# EEZ_DIB_BP3C_r1B4.net
KiCad netlist of a schematic drawn in EAGLE
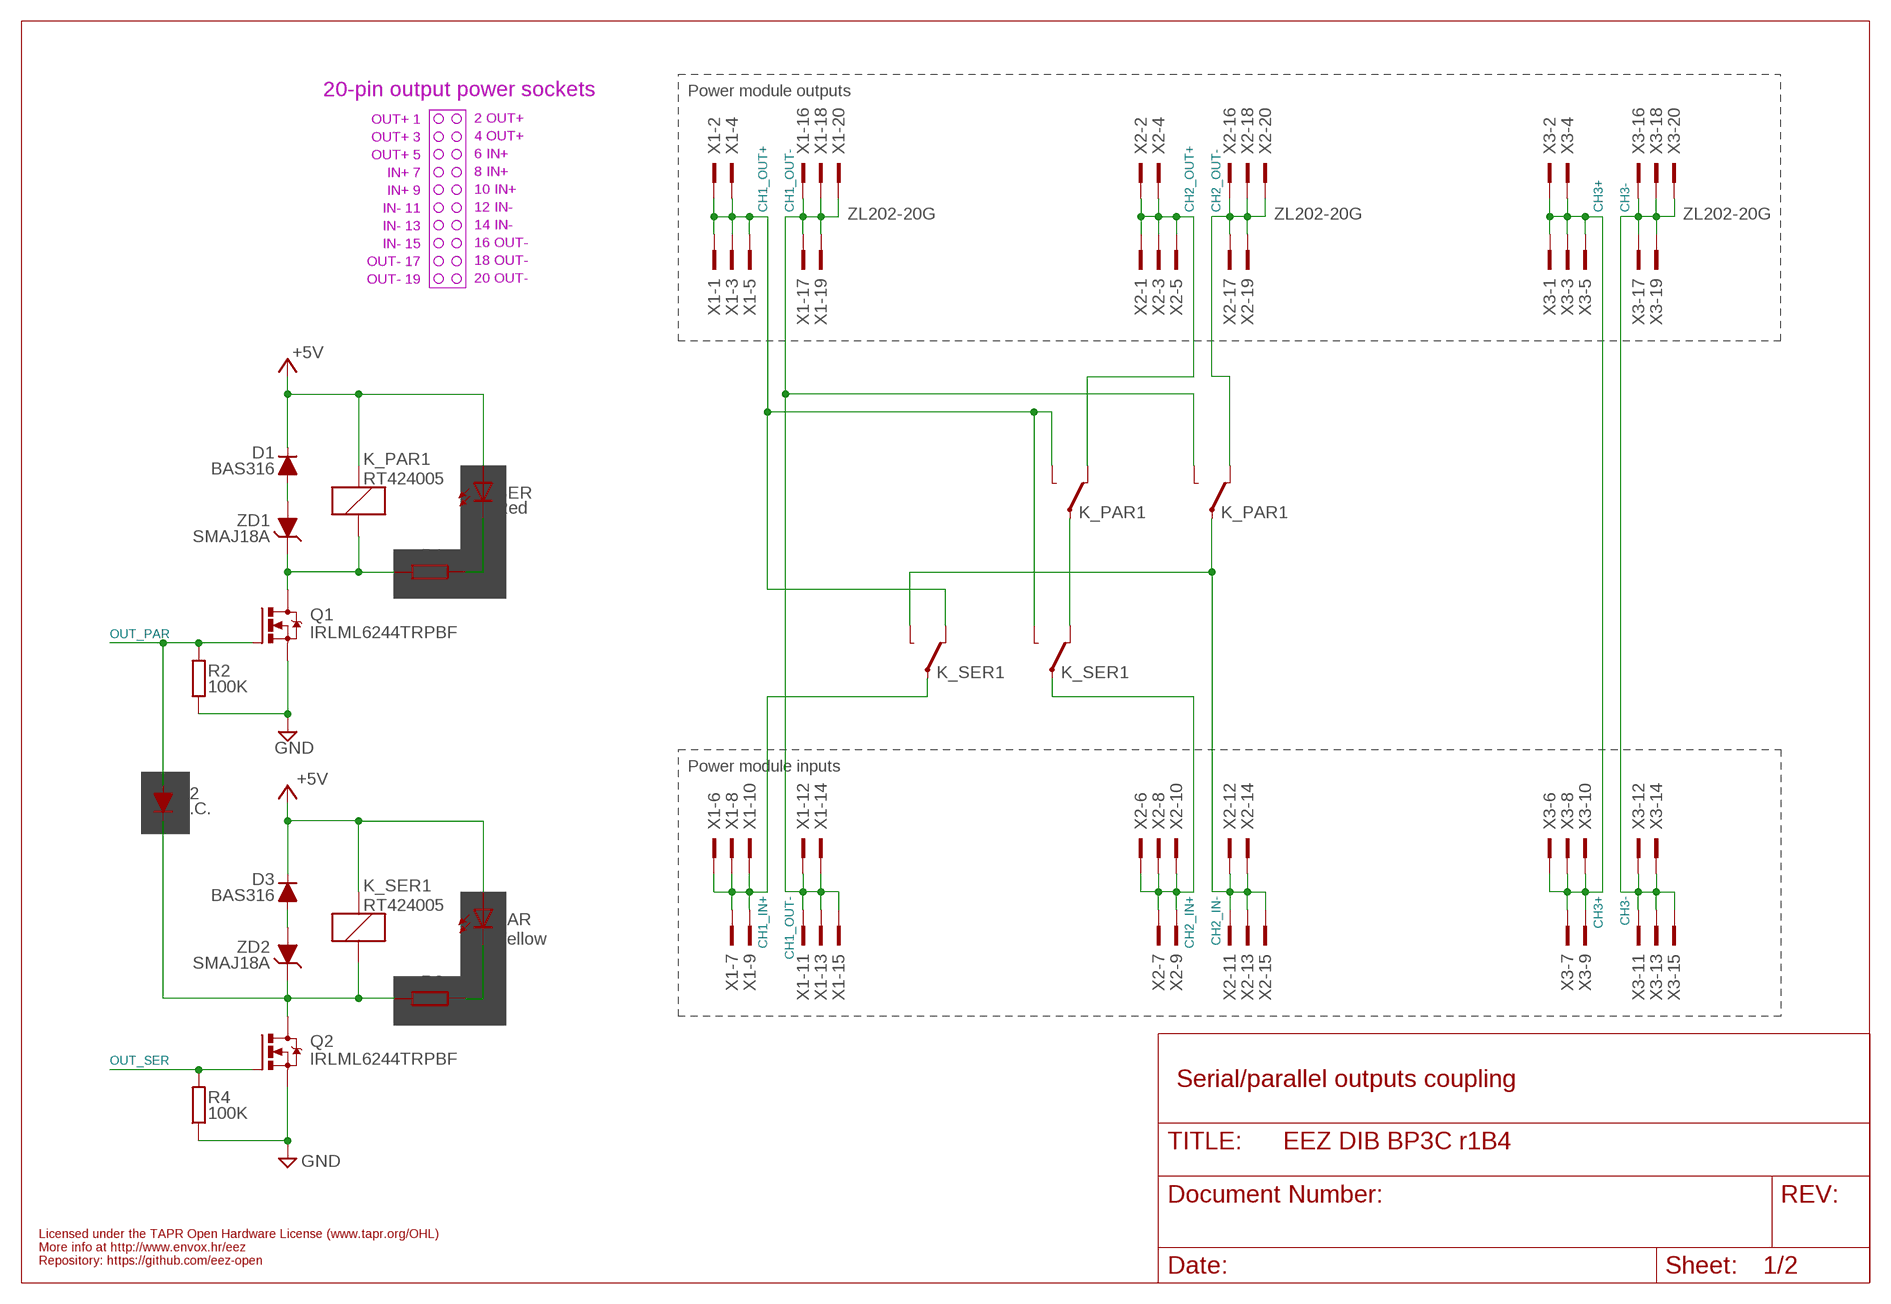
[diagram p0: schematic, sheet 1]
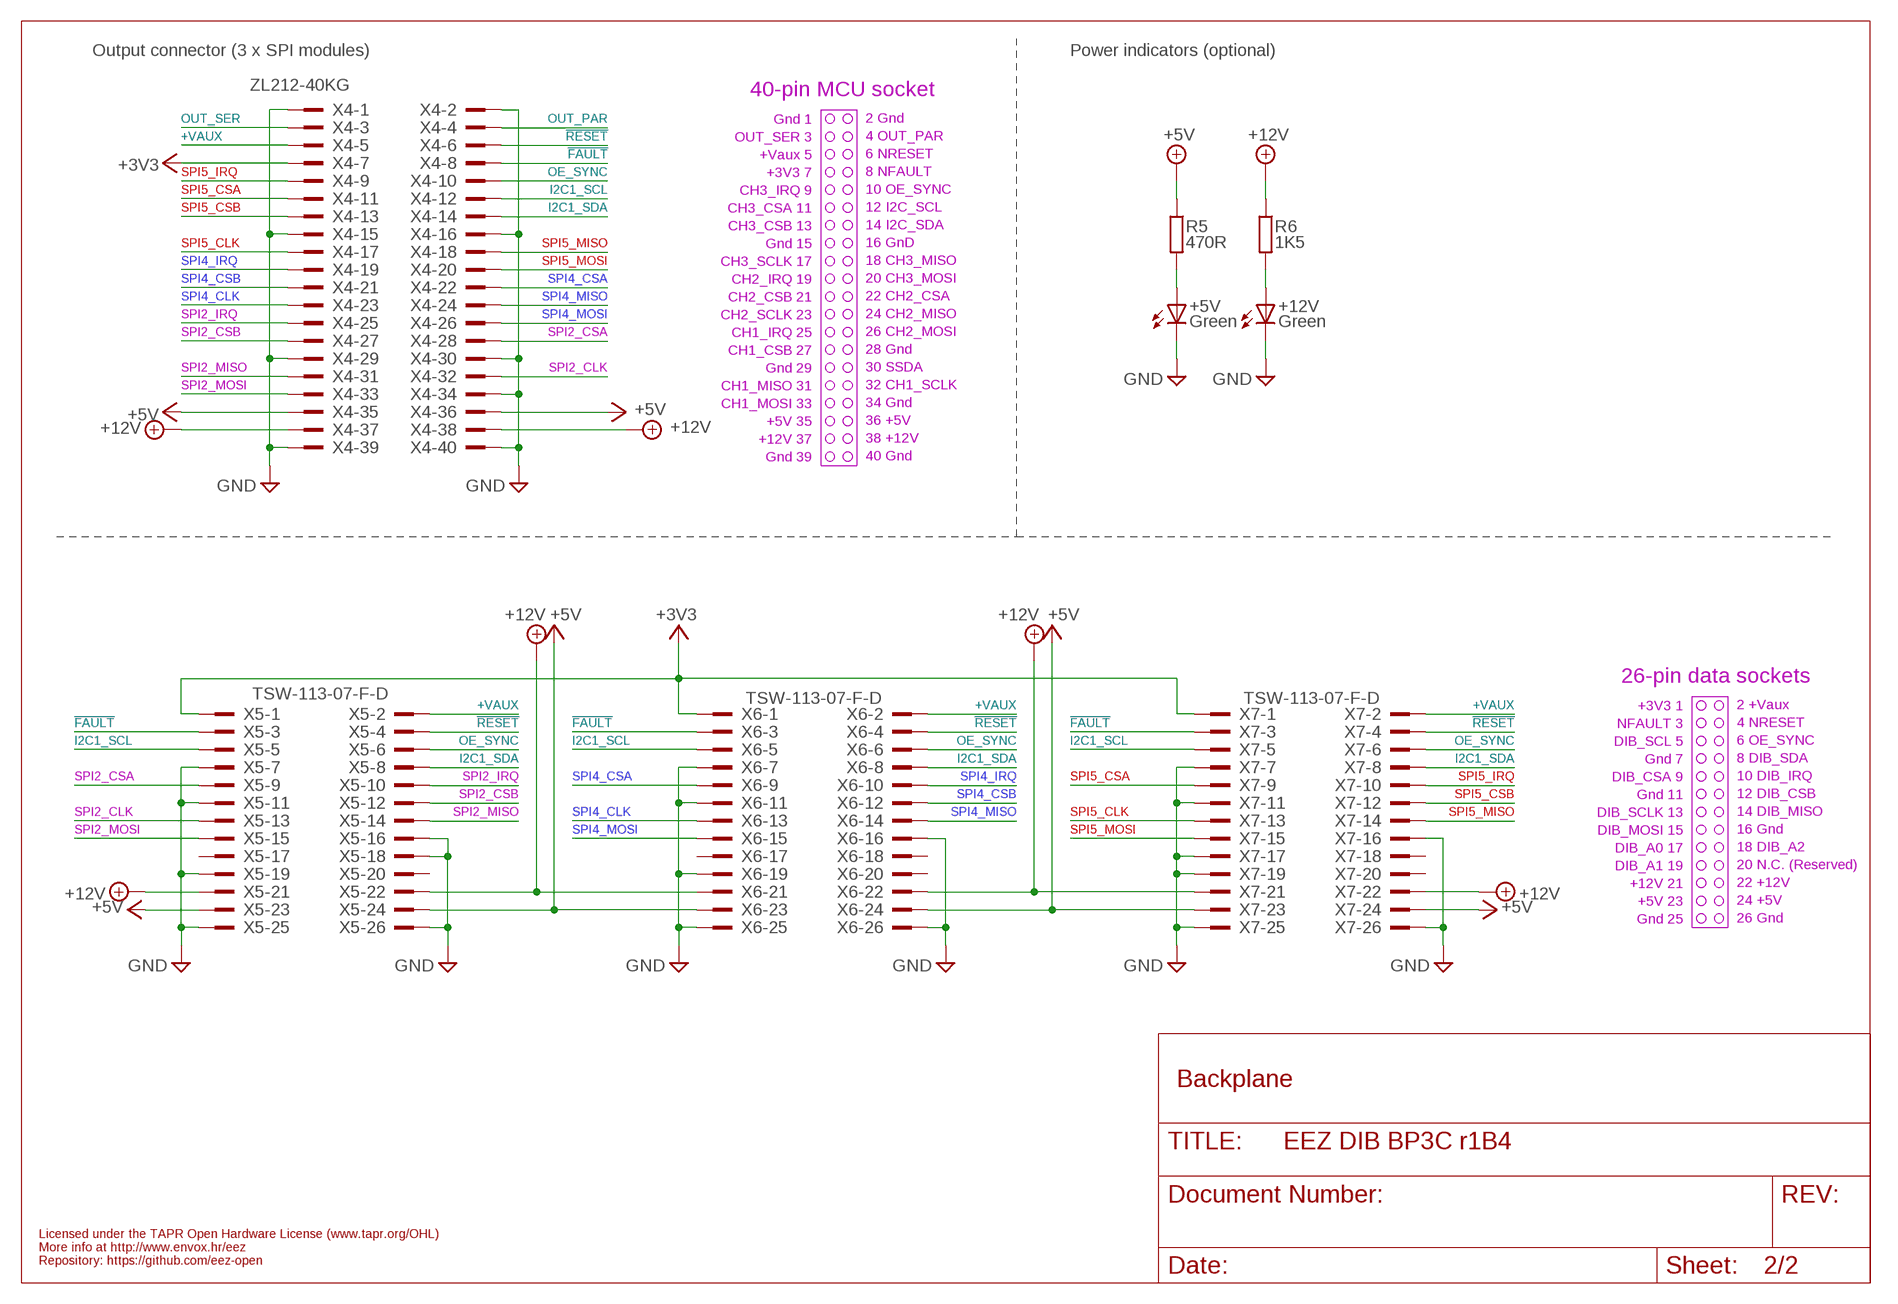
[diagram p1: schematic, sheet 2]

(export (version "E")
  (design (tool "Eeschema 10.0.6"))
  (components
    (comp (ref "+5V")
      (value "Green")
      (footprint "eagle-import:LED_0805")
      (libsource (lib "eagle-import") (part "LED0805"))
    )
    (comp (ref "+12V")
      (value "Green")
      (footprint "eagle-import:LED_0805")
      (libsource (lib "eagle-import") (part "LED0805"))
    )
    (comp (ref "R5")
      (value "470R")
      (footprint "eagle-import:R0805")
      (libsource (lib "eagle-import") (part "R-EU_R0805"))
    )
    (comp (ref "R6")
      (value "1K5")
      (footprint "eagle-import:R0805")
      (libsource (lib "eagle-import") (part "R-EU_R0805"))
    )
    (comp (ref "X4")
      (value "ZL212-40KG")
      (footprint "eagle-import:ZL212-40KG")
      (libsource (lib "eagle-import") (part "ZL212-40KG"))
    )
    (comp (ref "X5")
      (value "TSW-113-07-F-D")
      (footprint "eagle-import:TSW-113-07-F-D")
      (libsource (lib "eagle-import") (part "TSW-113-07-F-D"))
    )
    (comp (ref "X6")
      (value "TSW-113-07-F-D")
      (footprint "eagle-import:TSW-113-07-F-D")
      (libsource (lib "eagle-import") (part "TSW-113-07-F-D"))
    )
    (comp (ref "X7")
      (value "TSW-113-07-F-D")
      (footprint "eagle-import:TSW-113-07-F-D")
      (libsource (lib "eagle-import") (part "TSW-113-07-F-D"))
    )
    (comp (ref "D1")
      (value "BAS316")
      (footprint "eagle-import:SOD323-R")
      (libsource (lib "eagle-import") (part "DIODESOD323R"))
    )
    (comp (ref "D2")
      (value "N.C.")
      (footprint "eagle-import:SOD323-R")
      (libsource (lib "eagle-import") (part "DIODESOD323R"))
    )
    (comp (ref "D3")
      (value "BAS316")
      (footprint "eagle-import:SOD323-R")
      (libsource (lib "eagle-import") (part "DIODESOD323R"))
    )
    (comp (ref "K_PAR1")
      (value "RT424005")
      (footprint "eagle-import:RT-C_016A5_ROUND")
      (libsource (lib "eagle-import") (part "RELAY_RT314012-2"))
    )
    (comp (ref "K_SER1")
      (value "RT424005")
      (footprint "eagle-import:RT-C_016A5_ROUND")
      (libsource (lib "eagle-import") (part "RELAY_RT314012-2"))
    )
    (comp (ref "PAR")
      (value "Yellow")
      (footprint "eagle-import:LED_0805")
      (libsource (lib "eagle-import") (part "LED0805"))
    )
    (comp (ref "Q1")
      (value "IRLML6244TRPBF")
      (footprint "eagle-import:SOT103P240X110-3N")
      (fields
        (field (name "MPN") "2N7002-7-F")
        (field (name "MPN_1") "2N7002-7-F")
        (field (name "OC_FARNELL") "1713823")
        (field (name "OC_NEWARK") "25R5679")
        (field (name "PACKAGE") "SOT-23-3")
        (field (name "SUPPLIER") "DIODES INC.")
      )
      (libsource (lib "eagle-import") (part "2N7002"))
    )
    (comp (ref "Q2")
      (value "IRLML6244TRPBF")
      (footprint "eagle-import:SOT103P240X110-3N")
      (fields
        (field (name "MPN") "2N7002-7-F")
        (field (name "MPN_1") "2N7002-7-F")
        (field (name "OC_FARNELL") "1713823")
        (field (name "OC_NEWARK") "25R5679")
        (field (name "PACKAGE") "SOT-23-3")
        (field (name "SUPPLIER") "DIODES INC.")
      )
      (libsource (lib "eagle-import") (part "2N7002"))
    )
    (comp (ref "R1")
      (value "330R")
      (footprint "eagle-import:R0805")
      (libsource (lib "eagle-import") (part "R-EU_R0805"))
    )
    (comp (ref "R2")
      (value "100K")
      (footprint "eagle-import:R0805")
      (libsource (lib "eagle-import") (part "R-EU_R0805"))
    )
    (comp (ref "R3")
      (value "330R")
      (footprint "eagle-import:R0805")
      (libsource (lib "eagle-import") (part "R-EU_R0805"))
    )
    (comp (ref "R4")
      (value "100K")
      (footprint "eagle-import:R0805")
      (libsource (lib "eagle-import") (part "R-EU_R0805"))
    )
    (comp (ref "SER")
      (value "Red")
      (footprint "eagle-import:LED_0805")
      (libsource (lib "eagle-import") (part "LED0805"))
    )
    (comp (ref "X1")
      (value "ZL202-20G")
      (footprint "eagle-import:DS1021-2_10SF11")
      (libsource (lib "eagle-import") (part "DS1021-210SF11"))
    )
    (comp (ref "X2")
      (value "ZL202-20G")
      (footprint "eagle-import:DS1021-2_10SF11")
      (libsource (lib "eagle-import") (part "DS1021-210SF11"))
    )
    (comp (ref "X3")
      (value "ZL202-20G")
      (footprint "eagle-import:DS1021-2_10SF11")
      (libsource (lib "eagle-import") (part "DS1021-210SF11"))
    )
    (comp (ref "ZD1")
      (value "SMAJ18A")
      (footprint "eagle-import:DO214AC")
      (libsource (lib "eagle-import") (part "PSMAXX"))
    )
    (comp (ref "ZD2")
      (value "SMAJ18A")
      (footprint "eagle-import:DO214AC")
      (libsource (lib "eagle-import") (part "PSMAXX"))
    )
  )
  (nets
    (net (code "1") (name "+3V3") (class "Default")
      (node (ref "X4") (pin "7") (pinfunction "1_7") (pintype "passive"))
      (node (ref "X5") (pin "1") (pinfunction "1_1") (pintype "passive"))
      (node (ref "X6") (pin "1") (pinfunction "1_1") (pintype "passive"))
      (node (ref "X7") (pin "1") (pinfunction "1_1") (pintype "passive"))
    )
    (net (code "2") (name "+5V") (class "Default")
      (node (ref "D1") (pin "C") (pinfunction "C_C") (pintype "passive"))
      (node (ref "D3") (pin "C") (pinfunction "C_C") (pintype "passive"))
      (node (ref "K_PAR1") (pin "A2") (pinfunction "C1_A2") (pintype "passive"))
      (node (ref "K_SER1") (pin "A2") (pinfunction "C1_A2") (pintype "passive"))
      (node (ref "PAR") (pin "A") (pinfunction "A_A") (pintype "passive"))
      (node (ref "R5") (pin "1") (pinfunction "1_1") (pintype "passive"))
      (node (ref "SER") (pin "A") (pinfunction "A_A") (pintype "passive"))
      (node (ref "X4") (pin "35") (pinfunction "1_35") (pintype "passive"))
      (node (ref "X4") (pin "36") (pinfunction "1_36") (pintype "passive"))
      (node (ref "X5") (pin "23") (pinfunction "1_23") (pintype "passive"))
      (node (ref "X5") (pin "24") (pinfunction "1_24") (pintype "passive"))
      (node (ref "X6") (pin "23") (pinfunction "1_23") (pintype "passive"))
      (node (ref "X6") (pin "24") (pinfunction "1_24") (pintype "passive"))
      (node (ref "X7") (pin "23") (pinfunction "1_23") (pintype "passive"))
      (node (ref "X7") (pin "24") (pinfunction "1_24") (pintype "passive"))
    )
    (net (code "3") (name "+12V") (class "Default")
      (node (ref "R6") (pin "1") (pinfunction "1_1") (pintype "passive"))
      (node (ref "X4") (pin "37") (pinfunction "1_37") (pintype "passive"))
      (node (ref "X4") (pin "38") (pinfunction "1_38") (pintype "passive"))
      (node (ref "X5") (pin "21") (pinfunction "1_21") (pintype "passive"))
      (node (ref "X5") (pin "22") (pinfunction "1_22") (pintype "passive"))
      (node (ref "X6") (pin "21") (pinfunction "1_21") (pintype "passive"))
      (node (ref "X6") (pin "22") (pinfunction "1_22") (pintype "passive"))
      (node (ref "X7") (pin "21") (pinfunction "1_21") (pintype "passive"))
      (node (ref "X7") (pin "22") (pinfunction "1_22") (pintype "passive"))
    )
    (net (code "4") (name "+VAUX") (class "Default")
      (node (ref "X4") (pin "5") (pinfunction "1_5") (pintype "passive"))
      (node (ref "X5") (pin "2") (pinfunction "1_2") (pintype "passive"))
      (node (ref "X6") (pin "2") (pinfunction "1_2") (pintype "passive"))
      (node (ref "X7") (pin "2") (pinfunction "1_2") (pintype "passive"))
    )
    (net (code "5") (name "CH1_IN+") (class "Default")
      (node (ref "K_SER1") (pin "11A") (pinfunction "P_11A") (pintype "passive"))
      (node (ref "X1") (pin "10") (pinfunction "1_10") (pintype "passive"))
      (node (ref "X1") (pin "6") (pinfunction "1_6") (pintype "passive"))
      (node (ref "X1") (pin "7") (pinfunction "1_7") (pintype "passive"))
      (node (ref "X1") (pin "8") (pinfunction "1_8") (pintype "passive"))
      (node (ref "X1") (pin "9") (pinfunction "1_9") (pintype "passive"))
    )
    (net (code "6") (name "CH1_OUT+") (class "Default")
      (node (ref "K_PAR1") (pin "14A") (pinfunction "O_14A") (pintype "passive"))
      (node (ref "K_SER1") (pin "12A") (pinfunction "S_12A") (pintype "passive"))
      (node (ref "K_SER1") (pin "14B") (pinfunction "O_14B") (pintype "passive"))
      (node (ref "X1") (pin "1") (pinfunction "1_1") (pintype "passive"))
      (node (ref "X1") (pin "2") (pinfunction "1_2") (pintype "passive"))
      (node (ref "X1") (pin "3") (pinfunction "1_3") (pintype "passive"))
      (node (ref "X1") (pin "4") (pinfunction "1_4") (pintype "passive"))
      (node (ref "X1") (pin "5") (pinfunction "1_5") (pintype "passive"))
    )
    (net (code "7") (name "CH1_OUT-") (class "Default")
      (node (ref "K_PAR1") (pin "14B") (pinfunction "O_14B") (pintype "passive"))
      (node (ref "X1") (pin "11") (pinfunction "1_11") (pintype "passive"))
      (node (ref "X1") (pin "12") (pinfunction "1_12") (pintype "passive"))
      (node (ref "X1") (pin "13") (pinfunction "1_13") (pintype "passive"))
      (node (ref "X1") (pin "14") (pinfunction "1_14") (pintype "passive"))
      (node (ref "X1") (pin "15") (pinfunction "1_15") (pintype "passive"))
      (node (ref "X1") (pin "16") (pinfunction "1_16") (pintype "passive"))
      (node (ref "X1") (pin "17") (pinfunction "1_17") (pintype "passive"))
      (node (ref "X1") (pin "18") (pinfunction "1_18") (pintype "passive"))
      (node (ref "X1") (pin "19") (pinfunction "1_19") (pintype "passive"))
      (node (ref "X1") (pin "20") (pinfunction "1_20") (pintype "passive"))
    )
    (net (code "8") (name "CH2_IN+") (class "Default")
      (node (ref "K_SER1") (pin "11B") (pinfunction "P_11B") (pintype "passive"))
      (node (ref "X2") (pin "10") (pinfunction "1_10") (pintype "passive"))
      (node (ref "X2") (pin "6") (pinfunction "1_6") (pintype "passive"))
      (node (ref "X2") (pin "7") (pinfunction "1_7") (pintype "passive"))
      (node (ref "X2") (pin "8") (pinfunction "1_8") (pintype "passive"))
      (node (ref "X2") (pin "9") (pinfunction "1_9") (pintype "passive"))
    )
    (net (code "9") (name "CH2_IN-") (class "Default")
      (node (ref "K_PAR1") (pin "11B") (pinfunction "P_11B") (pintype "passive"))
      (node (ref "K_SER1") (pin "14A") (pinfunction "O_14A") (pintype "passive"))
      (node (ref "X2") (pin "11") (pinfunction "1_11") (pintype "passive"))
      (node (ref "X2") (pin "12") (pinfunction "1_12") (pintype "passive"))
      (node (ref "X2") (pin "13") (pinfunction "1_13") (pintype "passive"))
      (node (ref "X2") (pin "14") (pinfunction "1_14") (pintype "passive"))
      (node (ref "X2") (pin "15") (pinfunction "1_15") (pintype "passive"))
    )
    (net (code "10") (name "CH2_OUT+") (class "Default")
      (node (ref "K_PAR1") (pin "12A") (pinfunction "S_12A") (pintype "passive"))
      (node (ref "X2") (pin "1") (pinfunction "1_1") (pintype "passive"))
      (node (ref "X2") (pin "2") (pinfunction "1_2") (pintype "passive"))
      (node (ref "X2") (pin "3") (pinfunction "1_3") (pintype "passive"))
      (node (ref "X2") (pin "4") (pinfunction "1_4") (pintype "passive"))
      (node (ref "X2") (pin "5") (pinfunction "1_5") (pintype "passive"))
    )
    (net (code "11") (name "CH2_OUT-") (class "Default")
      (node (ref "K_PAR1") (pin "12B") (pinfunction "S_12B") (pintype "passive"))
      (node (ref "X2") (pin "16") (pinfunction "1_16") (pintype "passive"))
      (node (ref "X2") (pin "17") (pinfunction "1_17") (pintype "passive"))
      (node (ref "X2") (pin "18") (pinfunction "1_18") (pintype "passive"))
      (node (ref "X2") (pin "19") (pinfunction "1_19") (pintype "passive"))
      (node (ref "X2") (pin "20") (pinfunction "1_20") (pintype "passive"))
    )
    (net (code "12") (name "CH3+") (class "Default")
      (node (ref "X3") (pin "1") (pinfunction "1_1") (pintype "passive"))
      (node (ref "X3") (pin "10") (pinfunction "1_10") (pintype "passive"))
      (node (ref "X3") (pin "2") (pinfunction "1_2") (pintype "passive"))
      (node (ref "X3") (pin "3") (pinfunction "1_3") (pintype "passive"))
      (node (ref "X3") (pin "4") (pinfunction "1_4") (pintype "passive"))
      (node (ref "X3") (pin "5") (pinfunction "1_5") (pintype "passive"))
      (node (ref "X3") (pin "6") (pinfunction "1_6") (pintype "passive"))
      (node (ref "X3") (pin "7") (pinfunction "1_7") (pintype "passive"))
      (node (ref "X3") (pin "8") (pinfunction "1_8") (pintype "passive"))
      (node (ref "X3") (pin "9") (pinfunction "1_9") (pintype "passive"))
    )
    (net (code "13") (name "CH3-") (class "Default")
      (node (ref "X3") (pin "11") (pinfunction "1_11") (pintype "passive"))
      (node (ref "X3") (pin "12") (pinfunction "1_12") (pintype "passive"))
      (node (ref "X3") (pin "13") (pinfunction "1_13") (pintype "passive"))
      (node (ref "X3") (pin "14") (pinfunction "1_14") (pintype "passive"))
      (node (ref "X3") (pin "15") (pinfunction "1_15") (pintype "passive"))
      (node (ref "X3") (pin "16") (pinfunction "1_16") (pintype "passive"))
      (node (ref "X3") (pin "17") (pinfunction "1_17") (pintype "passive"))
      (node (ref "X3") (pin "18") (pinfunction "1_18") (pintype "passive"))
      (node (ref "X3") (pin "19") (pinfunction "1_19") (pintype "passive"))
      (node (ref "X3") (pin "20") (pinfunction "1_20") (pintype "passive"))
    )
    (net (code "14") (name "GND") (class "Default")
      (node (ref "+12V") (pin "C") (pinfunction "C_C") (pintype "passive"))
      (node (ref "+5V") (pin "C") (pinfunction "C_C") (pintype "passive"))
      (node (ref "Q1") (pin "2") (pinfunction "S_2") (pintype "passive"))
      (node (ref "Q2") (pin "2") (pinfunction "S_2") (pintype "passive"))
      (node (ref "R2") (pin "1") (pinfunction "1_1") (pintype "passive"))
      (node (ref "R4") (pin "1") (pinfunction "1_1") (pintype "passive"))
      (node (ref "X4") (pin "1") (pinfunction "1_1") (pintype "passive"))
      (node (ref "X4") (pin "15") (pinfunction "1_15") (pintype "passive"))
      (node (ref "X4") (pin "16") (pinfunction "1_16") (pintype "passive"))
      (node (ref "X4") (pin "2") (pinfunction "1_2") (pintype "passive"))
      (node (ref "X4") (pin "29") (pinfunction "1_29") (pintype "passive"))
      (node (ref "X4") (pin "30") (pinfunction "1_30") (pintype "passive"))
      (node (ref "X4") (pin "34") (pinfunction "1_34") (pintype "passive"))
      (node (ref "X4") (pin "39") (pinfunction "1_39") (pintype "passive"))
      (node (ref "X4") (pin "40") (pinfunction "1_40") (pintype "passive"))
      (node (ref "X5") (pin "11") (pinfunction "1_11") (pintype "passive"))
      (node (ref "X5") (pin "16") (pinfunction "1_16") (pintype "passive"))
      (node (ref "X5") (pin "18") (pinfunction "1_18") (pintype "passive"))
      (node (ref "X5") (pin "19") (pinfunction "1_19") (pintype "passive"))
      (node (ref "X5") (pin "25") (pinfunction "1_25") (pintype "passive"))
      (node (ref "X5") (pin "26") (pinfunction "1_26") (pintype "passive"))
      (node (ref "X5") (pin "7") (pinfunction "1_7") (pintype "passive"))
      (node (ref "X6") (pin "11") (pinfunction "1_11") (pintype "passive"))
      (node (ref "X6") (pin "16") (pinfunction "1_16") (pintype "passive"))
      (node (ref "X6") (pin "19") (pinfunction "1_19") (pintype "passive"))
      (node (ref "X6") (pin "25") (pinfunction "1_25") (pintype "passive"))
      (node (ref "X6") (pin "26") (pinfunction "1_26") (pintype "passive"))
      (node (ref "X6") (pin "7") (pinfunction "1_7") (pintype "passive"))
      (node (ref "X7") (pin "11") (pinfunction "1_11") (pintype "passive"))
      (node (ref "X7") (pin "16") (pinfunction "1_16") (pintype "passive"))
      (node (ref "X7") (pin "17") (pinfunction "1_17") (pintype "passive"))
      (node (ref "X7") (pin "19") (pinfunction "1_19") (pintype "passive"))
      (node (ref "X7") (pin "25") (pinfunction "1_25") (pintype "passive"))
      (node (ref "X7") (pin "26") (pinfunction "1_26") (pintype "passive"))
      (node (ref "X7") (pin "7") (pinfunction "1_7") (pintype "passive"))
    )
    (net (code "15") (name "I2C1_SCL") (class "Default")
      (node (ref "X4") (pin "12") (pinfunction "1_12") (pintype "passive"))
      (node (ref "X5") (pin "5") (pinfunction "1_5") (pintype "passive"))
      (node (ref "X6") (pin "5") (pinfunction "1_5") (pintype "passive"))
      (node (ref "X7") (pin "5") (pinfunction "1_5") (pintype "passive"))
    )
    (net (code "16") (name "I2C1_SDA") (class "Default")
      (node (ref "X4") (pin "14") (pinfunction "1_14") (pintype "passive"))
      (node (ref "X5") (pin "8") (pinfunction "1_8") (pintype "passive"))
      (node (ref "X6") (pin "8") (pinfunction "1_8") (pintype "passive"))
      (node (ref "X7") (pin "8") (pinfunction "1_8") (pintype "passive"))
    )
    (net (code "17") (name "Net-(+5V-PadA)") (class "Default")
      (node (ref "+5V") (pin "A") (pinfunction "A_A") (pintype "passive"))
      (node (ref "R5") (pin "2") (pinfunction "2_2") (pintype "passive"))
    )
    (net (code "18") (name "Net-(+12V-PadA)") (class "Default")
      (node (ref "+12V") (pin "A") (pinfunction "A_A") (pintype "passive"))
      (node (ref "R6") (pin "2") (pinfunction "2_2") (pintype "passive"))
    )
    (net (code "19") (name "Net-(D1-PadA)") (class "Default")
      (node (ref "D1") (pin "A") (pinfunction "A_A") (pintype "passive"))
      (node (ref "ZD1") (pin "A") (pinfunction "A_A") (pintype "passive"))
    )
    (net (code "20") (name "Net-(D3-PadA)") (class "Default")
      (node (ref "D3") (pin "A") (pinfunction "A_A") (pintype "passive"))
      (node (ref "ZD2") (pin "A") (pinfunction "A_A") (pintype "passive"))
    )
    (net (code "21") (name "Net-(K_PAR1A-P)") (class "Default")
      (node (ref "K_PAR1") (pin "11A") (pinfunction "P_11A") (pintype "passive"))
      (node (ref "K_SER1") (pin "12B") (pinfunction "S_12B") (pintype "passive"))
    )
    (net (code "22") (name "Net-(K_PAR1C-C2)") (class "Default")
      (node (ref "K_PAR1") (pin "A1") (pinfunction "C2_A1") (pintype "passive"))
      (node (ref "Q1") (pin "3") (pinfunction "D_3") (pintype "passive"))
      (node (ref "R1") (pin "2") (pinfunction "2_2") (pintype "passive"))
      (node (ref "ZD1") (pin "C") (pinfunction "C_C") (pintype "passive"))
    )
    (net (code "23") (name "Net-(K_SER1C-C2)") (class "Default")
      (node (ref "D2") (pin "C") (pinfunction "C_C") (pintype "passive"))
      (node (ref "K_SER1") (pin "A1") (pinfunction "C2_A1") (pintype "passive"))
      (node (ref "Q2") (pin "3") (pinfunction "D_3") (pintype "passive"))
      (node (ref "R3") (pin "2") (pinfunction "2_2") (pintype "passive"))
      (node (ref "ZD2") (pin "C") (pinfunction "C_C") (pintype "passive"))
    )
    (net (code "24") (name "Net-(PAR-PadC)") (class "Default")
      (node (ref "PAR") (pin "C") (pinfunction "C_C") (pintype "passive"))
      (node (ref "R3") (pin "1") (pinfunction "1_1") (pintype "passive"))
    )
    (net (code "25") (name "Net-(R1-Pad1)") (class "Default")
      (node (ref "R1") (pin "1") (pinfunction "1_1") (pintype "passive"))
      (node (ref "SER") (pin "C") (pinfunction "C_C") (pintype "passive"))
    )
    (net (code "26") (name "OE_SYNC") (class "Default")
      (node (ref "X4") (pin "10") (pinfunction "1_10") (pintype "passive"))
      (node (ref "X5") (pin "6") (pinfunction "1_6") (pintype "passive"))
      (node (ref "X6") (pin "6") (pinfunction "1_6") (pintype "passive"))
      (node (ref "X7") (pin "6") (pinfunction "1_6") (pintype "passive"))
    )
    (net (code "27") (name "OUT_PAR") (class "Default")
      (node (ref "D2") (pin "A") (pinfunction "A_A") (pintype "passive"))
      (node (ref "Q1") (pin "1") (pinfunction "G_1") (pintype "passive"))
      (node (ref "R2") (pin "2") (pinfunction "2_2") (pintype "passive"))
      (node (ref "X4") (pin "4") (pinfunction "1_4") (pintype "passive"))
    )
    (net (code "28") (name "OUT_SER") (class "Default")
      (node (ref "Q2") (pin "1") (pinfunction "G_1") (pintype "passive"))
      (node (ref "R4") (pin "2") (pinfunction "2_2") (pintype "passive"))
      (node (ref "X4") (pin "3") (pinfunction "1_3") (pintype "passive"))
    )
    (net (code "29") (name "SPI2_CLK") (class "Default")
      (node (ref "X4") (pin "32") (pinfunction "1_32") (pintype "passive"))
      (node (ref "X5") (pin "13") (pinfunction "1_13") (pintype "passive"))
    )
    (net (code "30") (name "SPI2_CSA") (class "Default")
      (node (ref "X4") (pin "28") (pinfunction "1_28") (pintype "passive"))
      (node (ref "X5") (pin "9") (pinfunction "1_9") (pintype "passive"))
    )
    (net (code "31") (name "SPI2_CSB") (class "Default")
      (node (ref "X4") (pin "27") (pinfunction "1_27") (pintype "passive"))
      (node (ref "X5") (pin "12") (pinfunction "1_12") (pintype "passive"))
    )
    (net (code "32") (name "SPI2_IRQ") (class "Default")
      (node (ref "X4") (pin "25") (pinfunction "1_25") (pintype "passive"))
      (node (ref "X5") (pin "10") (pinfunction "1_10") (pintype "passive"))
    )
    (net (code "33") (name "SPI2_MISO") (class "Default")
      (node (ref "X4") (pin "31") (pinfunction "1_31") (pintype "passive"))
      (node (ref "X5") (pin "14") (pinfunction "1_14") (pintype "passive"))
    )
    (net (code "34") (name "SPI2_MOSI") (class "Default")
      (node (ref "X4") (pin "33") (pinfunction "1_33") (pintype "passive"))
      (node (ref "X5") (pin "15") (pinfunction "1_15") (pintype "passive"))
    )
    (net (code "35") (name "SPI4_CLK") (class "Default")
      (node (ref "X4") (pin "23") (pinfunction "1_23") (pintype "passive"))
      (node (ref "X6") (pin "13") (pinfunction "1_13") (pintype "passive"))
    )
    (net (code "36") (name "SPI4_CSA") (class "Default")
      (node (ref "X4") (pin "22") (pinfunction "1_22") (pintype "passive"))
      (node (ref "X6") (pin "9") (pinfunction "1_9") (pintype "passive"))
    )
    (net (code "37") (name "SPI4_CSB") (class "Default")
      (node (ref "X4") (pin "21") (pinfunction "1_21") (pintype "passive"))
      (node (ref "X6") (pin "12") (pinfunction "1_12") (pintype "passive"))
    )
    (net (code "38") (name "SPI4_IRQ") (class "Default")
      (node (ref "X4") (pin "19") (pinfunction "1_19") (pintype "passive"))
      (node (ref "X6") (pin "10") (pinfunction "1_10") (pintype "passive"))
    )
    (net (code "39") (name "SPI4_MISO") (class "Default")
      (node (ref "X4") (pin "24") (pinfunction "1_24") (pintype "passive"))
      (node (ref "X6") (pin "14") (pinfunction "1_14") (pintype "passive"))
    )
    (net (code "40") (name "SPI4_MOSI") (class "Default")
      (node (ref "X4") (pin "26") (pinfunction "1_26") (pintype "passive"))
      (node (ref "X6") (pin "15") (pinfunction "1_15") (pintype "passive"))
    )
    (net (code "41") (name "SPI5_CLK") (class "Default")
      (node (ref "X4") (pin "17") (pinfunction "1_17") (pintype "passive"))
      (node (ref "X7") (pin "13") (pinfunction "1_13") (pintype "passive"))
    )
    (net (code "42") (name "SPI5_CSA") (class "Default")
      (node (ref "X4") (pin "11") (pinfunction "1_11") (pintype "passive"))
      (node (ref "X7") (pin "9") (pinfunction "1_9") (pintype "passive"))
    )
    (net (code "43") (name "SPI5_CSB") (class "Default")
      (node (ref "X4") (pin "13") (pinfunction "1_13") (pintype "passive"))
      (node (ref "X7") (pin "12") (pinfunction "1_12") (pintype "passive"))
    )
    (net (code "44") (name "SPI5_IRQ") (class "Default")
      (node (ref "X4") (pin "9") (pinfunction "1_9") (pintype "passive"))
      (node (ref "X7") (pin "10") (pinfunction "1_10") (pintype "passive"))
    )
    (net (code "45") (name "SPI5_MISO") (class "Default")
      (node (ref "X4") (pin "18") (pinfunction "1_18") (pintype "passive"))
      (node (ref "X7") (pin "14") (pinfunction "1_14") (pintype "passive"))
    )
    (net (code "46") (name "SPI5_MOSI") (class "Default")
      (node (ref "X4") (pin "20") (pinfunction "1_20") (pintype "passive"))
      (node (ref "X7") (pin "15") (pinfunction "1_15") (pintype "passive"))
    )
    (net (code "47") (name "unconnected-(X5I-1-Pad17)") (class "Default")
      (node (ref "X5") (pin "17") (pinfunction "1_17") (pintype "passive"))
    )
    (net (code "48") (name "unconnected-(X5M-1-Pad20)") (class "Default")
      (node (ref "X5") (pin "20") (pinfunction "1_20") (pintype "passive"))
    )
    (net (code "49") (name "unconnected-(X6I-1-Pad17)") (class "Default")
      (node (ref "X6") (pin "17") (pinfunction "1_17") (pintype "passive"))
    )
    (net (code "50") (name "unconnected-(X6J-1-Pad18)") (class "Default")
      (node (ref "X6") (pin "18") (pinfunction "1_18") (pintype "passive"))
    )
    (net (code "51") (name "unconnected-(X6M-1-Pad20)") (class "Default")
      (node (ref "X6") (pin "20") (pinfunction "1_20") (pintype "passive"))
    )
    (net (code "52") (name "unconnected-(X7J-1-Pad18)") (class "Default")
      (node (ref "X7") (pin "18") (pinfunction "1_18") (pintype "passive"))
    )
    (net (code "53") (name "unconnected-(X7M-1-Pad20)") (class "Default")
      (node (ref "X7") (pin "20") (pinfunction "1_20") (pintype "passive"))
    )
    (net (code "54") (name "~{FAULT}") (class "Default")
      (node (ref "X4") (pin "8") (pinfunction "1_8") (pintype "passive"))
      (node (ref "X5") (pin "3") (pinfunction "1_3") (pintype "passive"))
      (node (ref "X6") (pin "3") (pinfunction "1_3") (pintype "passive"))
      (node (ref "X7") (pin "3") (pinfunction "1_3") (pintype "passive"))
    )
    (net (code "55") (name "~{RESET}") (class "Default")
      (node (ref "X4") (pin "6") (pinfunction "1_6") (pintype "passive"))
      (node (ref "X5") (pin "4") (pinfunction "1_4") (pintype "passive"))
      (node (ref "X6") (pin "4") (pinfunction "1_4") (pintype "passive"))
      (node (ref "X7") (pin "4") (pinfunction "1_4") (pintype "passive"))
    )
  )
)
